# Top.net
KiCad netlist of a schematic drawn in Altium Designer
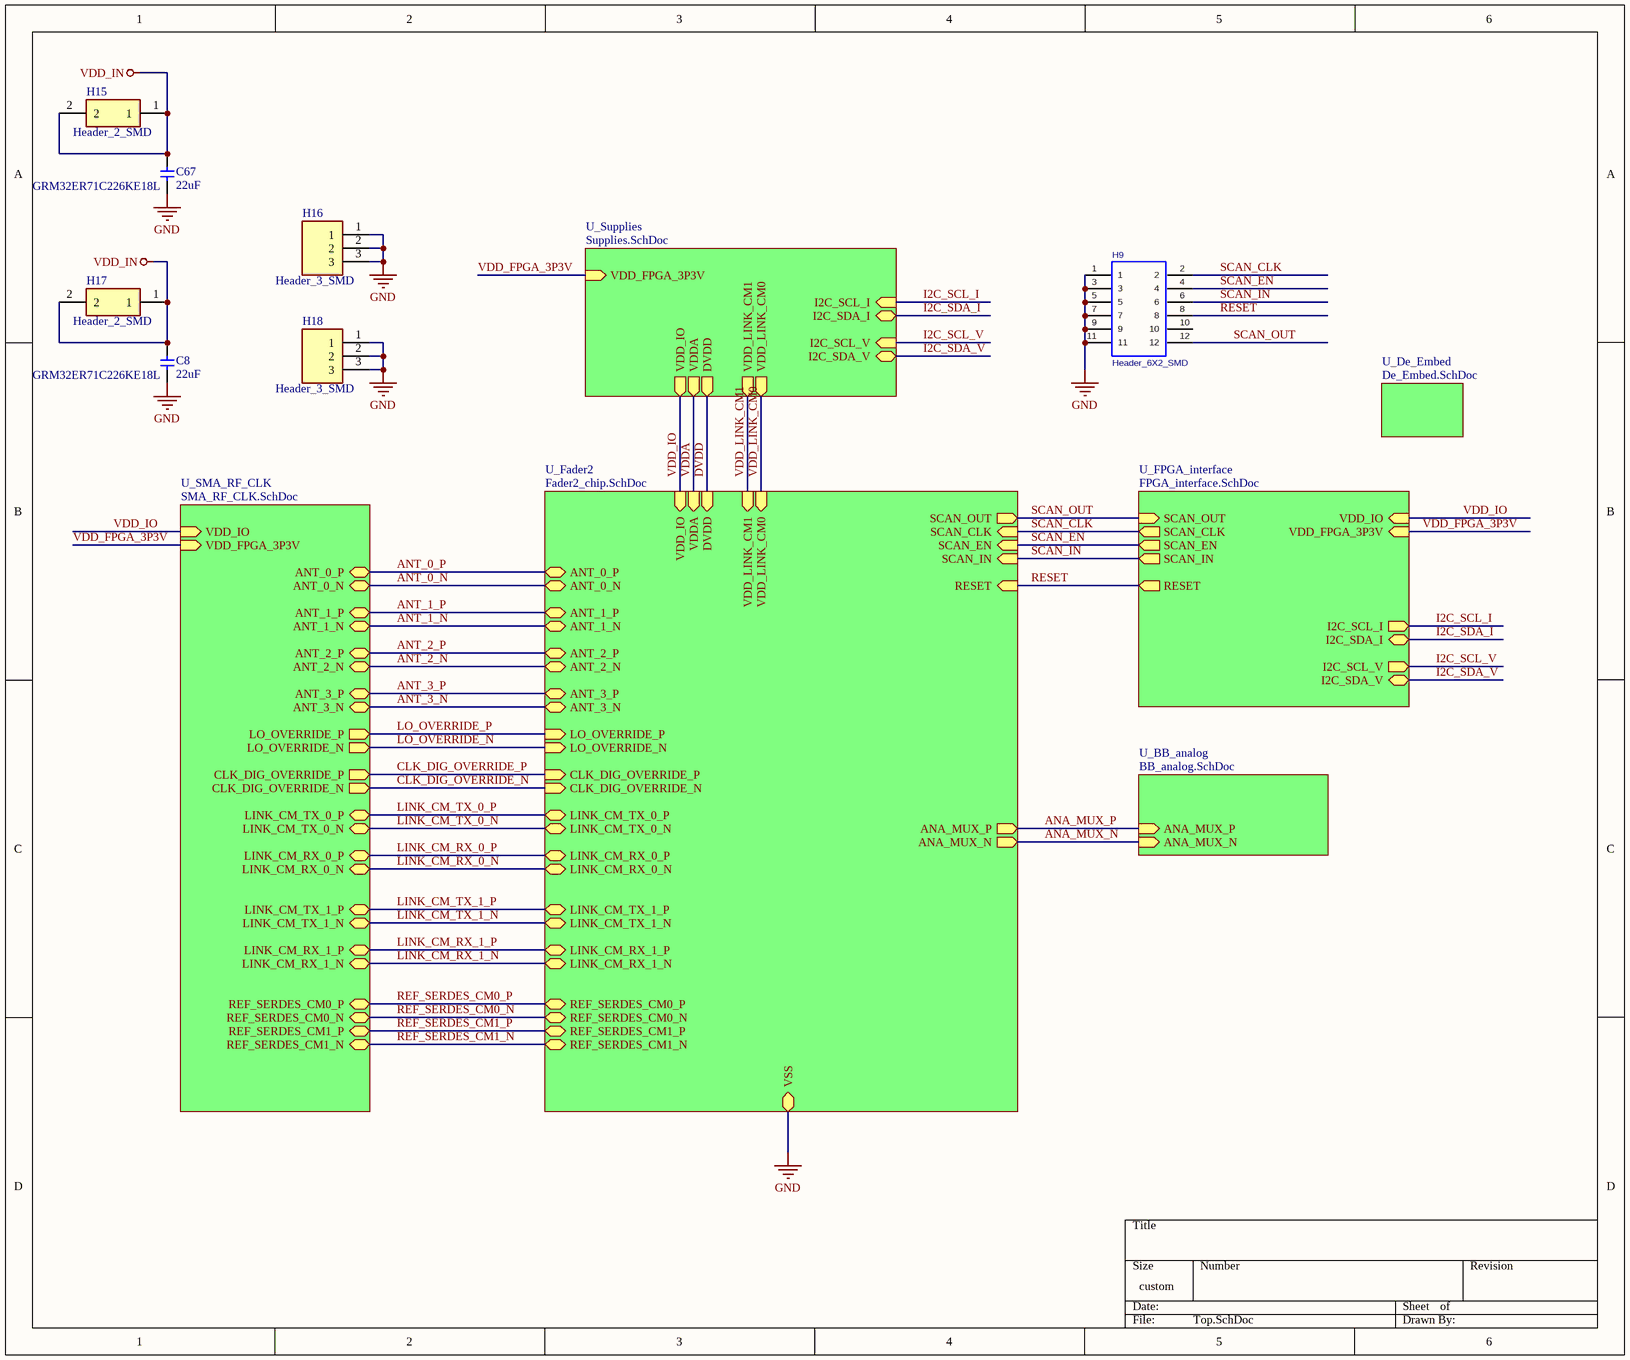
[diagram p0: Top.SchDoc]

(export (version "E")
  (design (tool "Eeschema 10.0.6"))
  (components
    (comp (ref "C8")
      (value "22uF")
      (footprint "CAPC3225X27N")
      (description "CAP CER 22uF 10% 16V X7R 1210")
      (fields
        (field (name "MANUFACTURER") "Murata")
        (field (name "SUPPLIER PART NUMBER 1") "GRM32ER71C226KE18L")
      )
      (libsource (lib "fader2_parts") (part "cap 22uF"))
    )
    (comp (ref "C67")
      (value "22uF")
      (footprint "CAPC3225X27N")
      (description "CAP CER 22uF 10% 16V X7R 1210")
      (fields
        (field (name "MANUFACTURER") "Murata")
        (field (name "SUPPLIER PART NUMBER 1") "GRM32ER71C226KE18L")
      )
      (libsource (lib "fader2_parts") (part "cap 22uF"))
    )
    (comp (ref "H9")
      (value "Header_6X2_SMD")
      (footprint "HDR2X6_SMD")
      (description "Connector Header Vertical Dual Row, SMD, 12 position 0.100\" (2.54mm)")
      (fields (field (name "MANUFACTURER") "SAMTEC") (field (name "CREATED") "November 23, 2017 - Wendy Xin"))
      (libsource (lib "fader2_parts") (part "Header_6X2_SMD"))
    )
    (comp (ref "H15")
      (value "Header_2_SMD")
      (footprint "HDR1X2_SMD_S")
      (description "Connector Header Vertical, SMD, 2 position 0.100\" (2.54mm)")
      (fields
        (field (name "MANUFACTURER_PART_NUMBER") "TSM-102-01-S-SV")
        (field (name "MOUSER PART NUMBER") "200-TSM10201SSV")
      )
      (libsource (lib "fader2_parts") (part "Header_2_SMD"))
    )
    (comp (ref "H16")
      (value "Header_3_SMD")
      (footprint "HDR1X3_SMD")
      (description "Connector Header Vertical, SMD, 3 position 0.100\" (2.54mm)")
      (fields
        (field (name "MANUFACTURER_PART_NUMBER") "TSM-103-01-S-SV-P-TR")
        (field (name "MOUSER PART NUMBER") "200-TSM10301SSVPTR")
      )
      (libsource (lib "fader2_parts") (part "Header_3_SMD"))
    )
    (comp (ref "H17")
      (value "Header_2_SMD")
      (footprint "HDR1X2_SMD_S")
      (description "Connector Header Vertical, SMD, 2 position 0.100\" (2.54mm)")
      (fields
        (field (name "MANUFACTURER_PART_NUMBER") "TSM-102-01-S-SV")
        (field (name "MOUSER PART NUMBER") "200-TSM10201SSV")
      )
      (libsource (lib "fader2_parts") (part "Header_2_SMD"))
    )
    (comp (ref "H18")
      (value "Header_3_SMD")
      (footprint "HDR1X3_SMD")
      (description "Connector Header Vertical, SMD, 3 position 0.100\" (2.54mm)")
      (fields
        (field (name "MANUFACTURER_PART_NUMBER") "TSM-103-01-S-SV-P-TR")
        (field (name "MOUSER PART NUMBER") "200-TSM10301SSVPTR")
      )
      (libsource (lib "fader2_parts") (part "Header_3_SMD"))
    )
  )
  (nets
    (net (code "32") (name "/RESET") (class "Default")
      (node (ref "H9") (pin "8") (pinfunction "8_8") (pintype "passive"))
    )
    (net (code "33") (name "/SCAN_CLK") (class "Default")
      (node (ref "H9") (pin "2") (pinfunction "2_2") (pintype "passive"))
    )
    (net (code "34") (name "/SCAN_EN") (class "Default")
      (node (ref "H9") (pin "4") (pinfunction "4_4") (pintype "passive"))
    )
    (net (code "35") (name "/SCAN_IN") (class "Default")
      (node (ref "H9") (pin "6") (pinfunction "6_6") (pintype "passive"))
    )
    (net (code "36") (name "/SCAN_OUT") (class "Default")
      (node (ref "H9") (pin "12") (pinfunction "12_12") (pintype "passive"))
    )
    (net (code "42") (name "GND") (class "Default")
      (node (ref "C67") (pin "2") (pinfunction "2_2") (pintype "passive"))
      (node (ref "C8") (pin "2") (pinfunction "2_2") (pintype "passive"))
      (node (ref "H16") (pin "1") (pinfunction "1_1") (pintype "passive"))
      (node (ref "H16") (pin "2") (pinfunction "2_2") (pintype "passive"))
      (node (ref "H16") (pin "3") (pinfunction "3_3") (pintype "passive"))
      (node (ref "H18") (pin "1") (pinfunction "1_1") (pintype "passive"))
      (node (ref "H18") (pin "2") (pinfunction "2_2") (pintype "passive"))
      (node (ref "H18") (pin "3") (pinfunction "3_3") (pintype "passive"))
      (node (ref "H9") (pin "1") (pinfunction "1_1") (pintype "passive"))
      (node (ref "H9") (pin "11") (pinfunction "11_11") (pintype "passive"))
      (node (ref "H9") (pin "3") (pinfunction "3_3") (pintype "passive"))
      (node (ref "H9") (pin "5") (pinfunction "5_5") (pintype "passive"))
      (node (ref "H9") (pin "7") (pinfunction "7_7") (pintype "passive"))
      (node (ref "H9") (pin "9") (pinfunction "9_9") (pintype "passive"))
    )
    (net (code "43") (name "VDD_IN") (class "Default")
      (node (ref "C67") (pin "1") (pinfunction "1_1") (pintype "passive"))
      (node (ref "C8") (pin "1") (pinfunction "1_1") (pintype "passive"))
      (node (ref "H15") (pin "1") (pinfunction "1_1") (pintype "passive"))
      (node (ref "H15") (pin "2") (pinfunction "2_2") (pintype "passive"))
      (node (ref "H17") (pin "1") (pinfunction "1_1") (pintype "passive"))
      (node (ref "H17") (pin "2") (pinfunction "2_2") (pintype "passive"))
    )
    (net (code "44") (name "unconnected-(H9-Pad10)") (class "Default")
      (node (ref "H9") (pin "10") (pinfunction "10_10") (pintype "passive"))
    )
  )
)
